# STM32_Board_with_IMU.net
KiCad netlist of a schematic drawn in Altium Designer
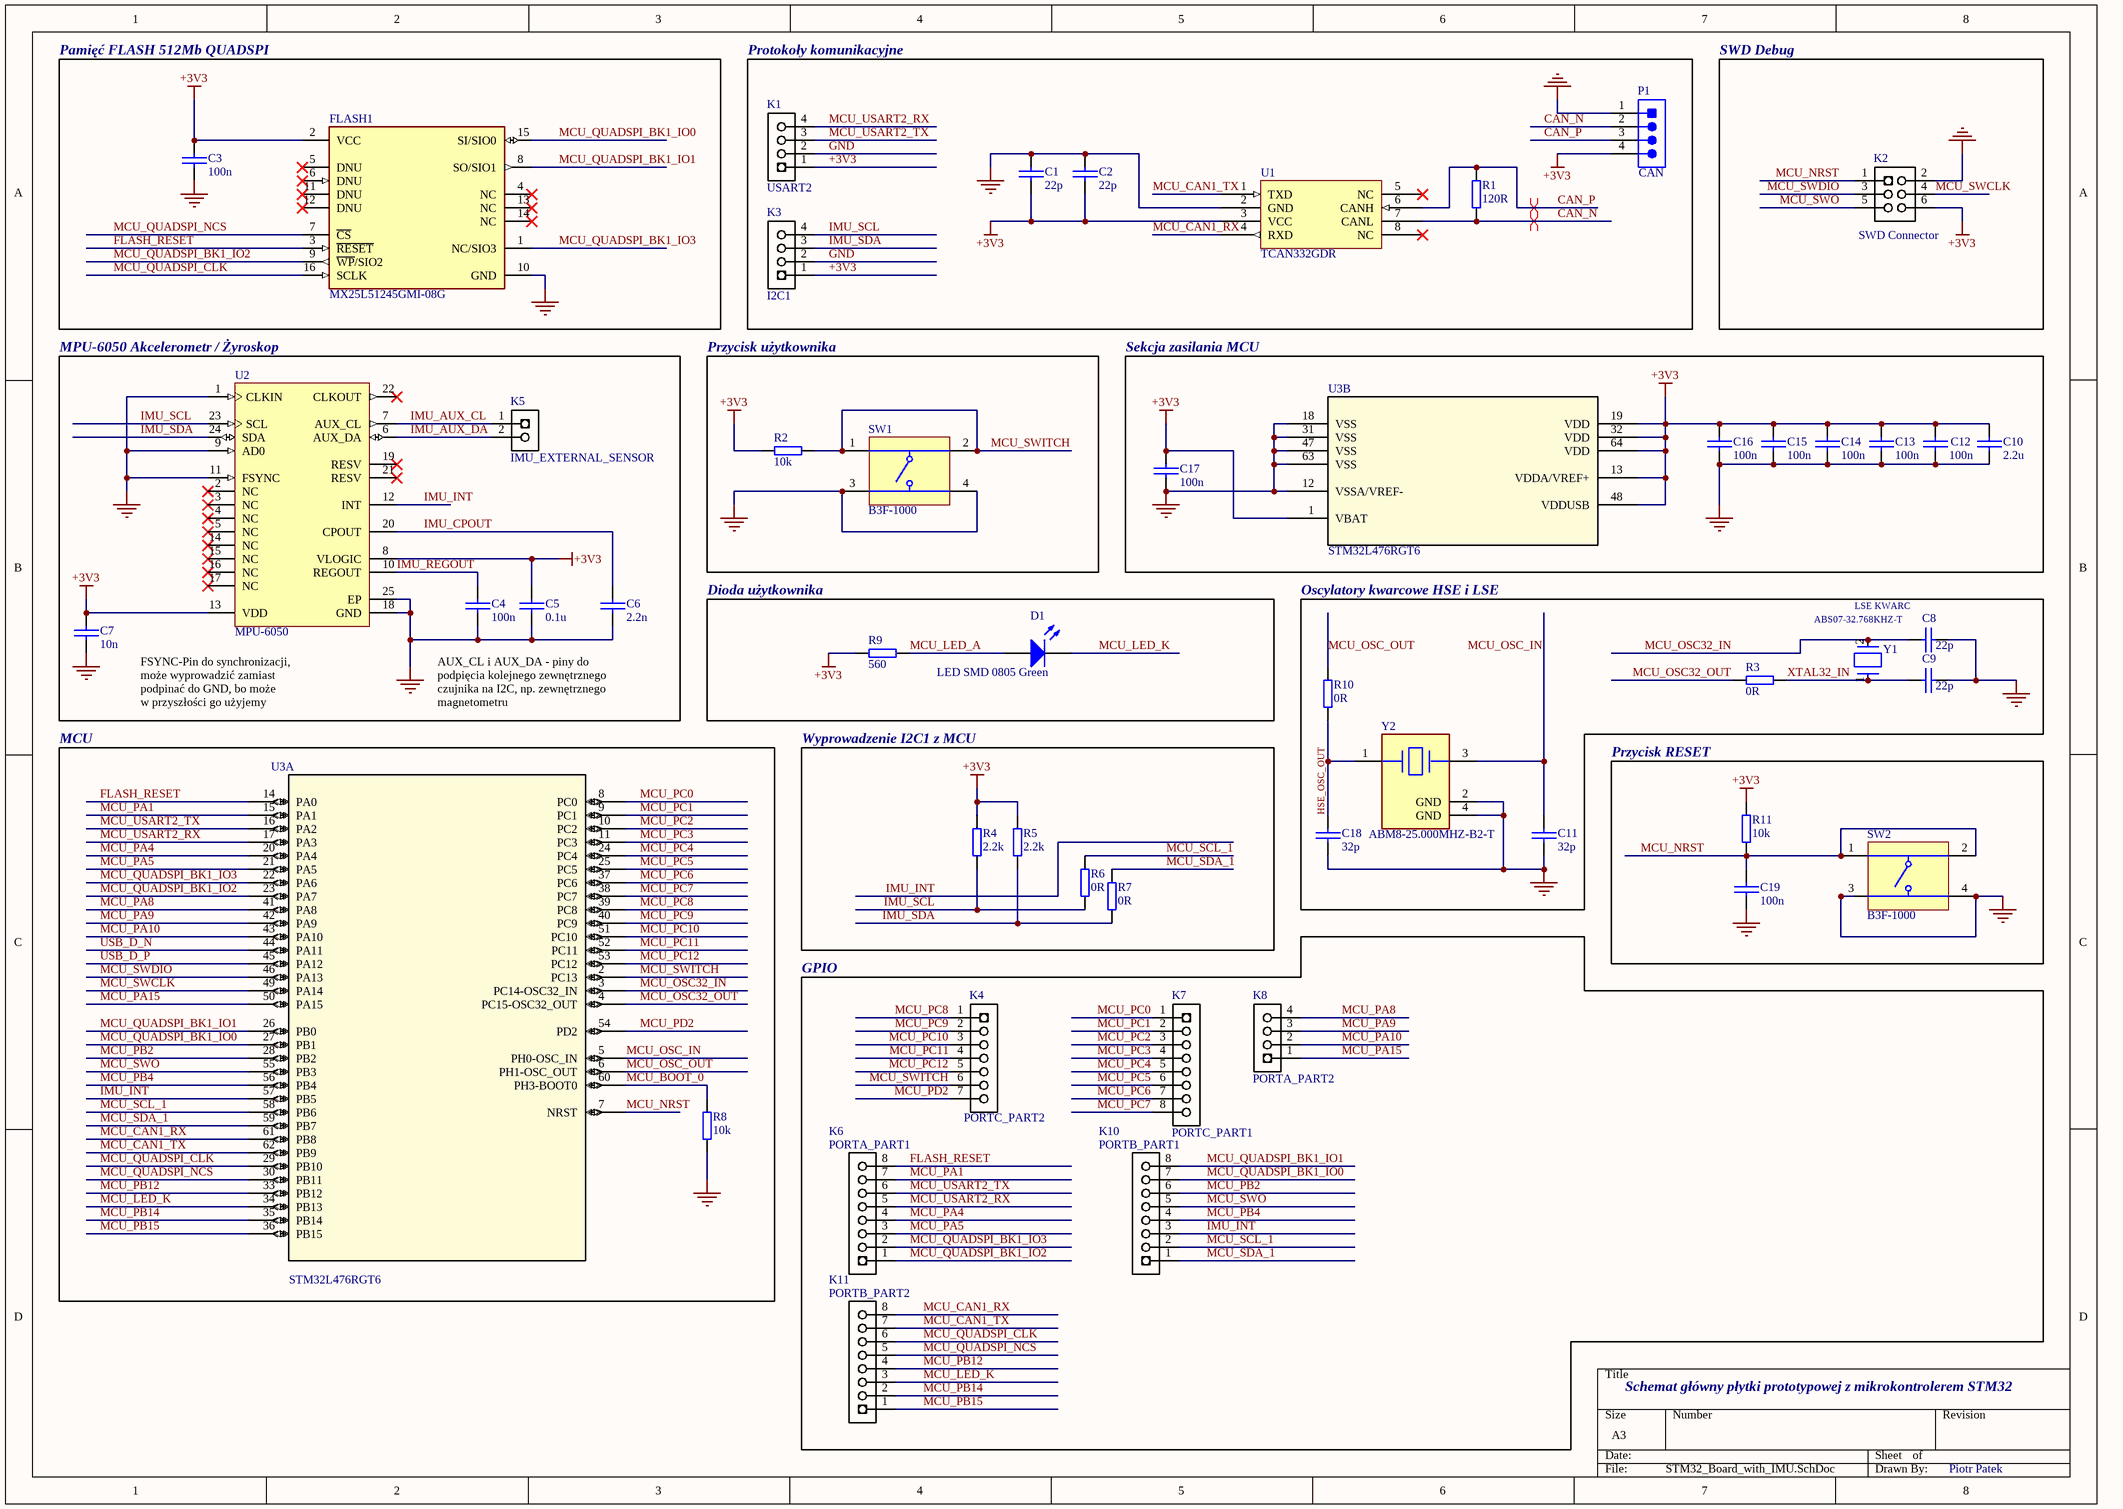
[diagram p0: STM32_Board_with_IMU.SchDoc]

(export (version "E")
  (design (tool "Eeschema 10.0.6"))
  (components
    (comp (ref "C1") (value "22p") (footprint "0805") (libsource (lib "Slawek_new") (part "Kondensator")))
    (comp (ref "C2") (value "22p") (footprint "0805") (libsource (lib "Slawek_new") (part "Kondensator")))
    (comp (ref "C3") (value "100n") (footprint "0805") (libsource (lib "Slawek_new") (part "Kondensator")))
    (comp (ref "C4") (value "100n") (footprint "0805") (libsource (lib "Slawek_new") (part "Kondensator")))
    (comp (ref "C5") (value "0.1u") (footprint "0805") (libsource (lib "Slawek_new") (part "Kondensator")))
    (comp (ref "C6") (value "2.2n") (footprint "0805") (libsource (lib "Slawek_new") (part "Kondensator")))
    (comp (ref "C7") (value "10n") (footprint "0805") (libsource (lib "Slawek_new") (part "Kondensator")))
    (comp (ref "C8") (value "22p") (footprint "0805") (libsource (lib "Slawek_new") (part "Kondensator")))
    (comp (ref "C9") (value "22p") (footprint "0805") (libsource (lib "Slawek_new") (part "Kondensator")))
    (comp (ref "C10") (value "2.2u") (footprint "0805") (libsource (lib "Slawek_new") (part "Kondensator")))
    (comp (ref "C11") (value "32p") (footprint "0805") (libsource (lib "Slawek_new") (part "Kondensator")))
    (comp (ref "C12") (value "100n") (footprint "0805") (libsource (lib "Slawek_new") (part "Kondensator")))
    (comp (ref "C13") (value "100n") (footprint "0805") (libsource (lib "Slawek_new") (part "Kondensator")))
    (comp (ref "C14") (value "100n") (footprint "0805") (libsource (lib "Slawek_new") (part "Kondensator")))
    (comp (ref "C15") (value "100n") (footprint "0805") (libsource (lib "Slawek_new") (part "Kondensator")))
    (comp (ref "C16") (value "100n") (footprint "0805") (libsource (lib "Slawek_new") (part "Kondensator")))
    (comp (ref "C17") (value "100n") (footprint "0805") (libsource (lib "Slawek_new") (part "Kondensator")))
    (comp (ref "C18") (value "32p") (footprint "0805") (libsource (lib "Slawek_new") (part "Kondensator")))
    (comp (ref "C19") (value "100n") (footprint "0805") (libsource (lib "Slawek_new") (part "Kondensator")))
    (comp (ref "D1")
      (value "LED SMD 0805 Green")
      (footprint "0805_PAD")
      (description "WURTH ELEKTRONIK - 150080GS75000 - LED, Green, SMD, 0805, 30 mA, 3.2 V, 520 nm")
      (fields
        (field (name "MANUFACTURER") "Wurth Electronics")
        (field (name "MANUFACTURER PART NUMBER") "150080GS75000")
      )
      (libsource (lib "BibliotekaPiotrek") (part "LED SMD 0805 Green"))
    )
    (comp (ref "FLASH1")
      (value "MX25L51245GMI-08G")
      (footprint "FP-MX25L51245GMI-08G-IPC_C")
      (description "IC FLASH 512MBIT SPI/QUAD 16SOP")
      (libsource (lib "Altium Content Vault") (part "66e4bce8553d63856ccc32a245ce7da"))
    )
    (comp (ref "K1")
      (value "USART2")
      (footprint "HEADER-1X4")
      (libsource (lib "vh_altium_library") (part "HEADER-1X4"))
    )
    (comp (ref "K2")
      (value "SWD Connector")
      (footprint "HEADER-2X3")
      (libsource (lib "vh_altium_library") (part "HEADER-2X3"))
    )
    (comp (ref "K3")
      (value "I2C1")
      (footprint "HEADER-1X4")
      (libsource (lib "vh_altium_library") (part "HEADER-1X4"))
    )
    (comp (ref "K4")
      (value "PORTC_PART2")
      (footprint "HEADER-1X7")
      (libsource (lib "vh_altium_library") (part "HEADER-1X7"))
    )
    (comp (ref "K5")
      (value "IMU_EXTERNAL_SENSOR")
      (footprint "HEADER-1X2")
      (libsource (lib "vh_altium_library") (part "HEADER-1X2"))
    )
    (comp (ref "K6")
      (value "PORTA_PART1")
      (footprint "HEADER-1X8")
      (libsource (lib "vh_altium_library") (part "HEADER-1X8"))
    )
    (comp (ref "K7")
      (value "PORTC_PART1")
      (footprint "HEADER-1X8")
      (libsource (lib "vh_altium_library") (part "HEADER-1X8"))
    )
    (comp (ref "K8")
      (value "PORTA_PART2")
      (footprint "HEADER-1X4")
      (libsource (lib "vh_altium_library") (part "HEADER-1X4"))
    )
    (comp (ref "K10")
      (value "PORTB_PART1")
      (footprint "HEADER-1X8")
      (libsource (lib "vh_altium_library") (part "HEADER-1X8"))
    )
    (comp (ref "K11")
      (value "PORTB_PART2")
      (footprint "HEADER-1X8")
      (libsource (lib "vh_altium_library") (part "HEADER-1X8"))
    )
    (comp (ref "P1")
      (value "CAN")
      (footprint "TECO-640456-4")
      (description "Male Header, Pitch 2.54 mm, 1 x 4 Position, Height 10.03 mm, Tail Length 3.56 mm, RoHS, Bulk")
      (fields (field (name "MANUFACTURER") "TE Connectivity"))
      (libsource (lib "Altium Content Vault") (part "CN-1P-M-R4"))
    )
    (comp (ref "R1") (value "120R") (footprint "0805") (libsource (lib "Slawek_new") (part "Rezystor")))
    (comp (ref "R2") (value "10k") (footprint "0805") (libsource (lib "Slawek_new") (part "Rezystor")))
    (comp (ref "R3") (value "0R") (footprint "0805") (libsource (lib "Slawek_new") (part "Rezystor")))
    (comp (ref "R4") (value "2.2k") (footprint "0805") (libsource (lib "Slawek_new") (part "Rezystor")))
    (comp (ref "R5") (value "2.2k") (footprint "0805") (libsource (lib "Slawek_new") (part "Rezystor")))
    (comp (ref "R6") (value "0R") (footprint "0805") (libsource (lib "Slawek_new") (part "Rezystor")))
    (comp (ref "R7") (value "0R") (footprint "0805") (libsource (lib "Slawek_new") (part "Rezystor")))
    (comp (ref "R8") (value "10k") (footprint "0805") (libsource (lib "Slawek_new") (part "Rezystor")))
    (comp (ref "R9") (value "560") (footprint "0805") (libsource (lib "Slawek_new") (part "Rezystor")))
    (comp (ref "R10") (value "0R") (footprint "0805") (libsource (lib "Slawek_new") (part "Rezystor")))
    (comp (ref "R11") (value "10k") (footprint "0805") (libsource (lib "Slawek_new") (part "Rezystor")))
    (comp (ref "SW1")
      (value "B3F-1000")
      (footprint "OMRON-B3F-1000-4_V")
      (description "Tactile Switch, SPST-NO, 0.05 A, 5 to 24 V, -25 to 70 degC, 4-Pin THD, RoHS, Bulk")
      (libsource (lib "Altium Content Vault") (part "SW-SPST-4_A"))
    )
    (comp (ref "SW2")
      (value "B3F-1000")
      (footprint "OMRON-B3F-1000-4_V")
      (description "Tactile Switch, SPST-NO, 0.05 A, 5 to 24 V, -25 to 70 degC, 4-Pin THD, RoHS, Bulk")
      (libsource (lib "Altium Content Vault") (part "SW-SPST-4_A"))
    )
    (comp (ref "U1")
      (value "TCAN332GDR")
      (footprint "SOIC-8_x1")
      (description "Can Transceiver")
      (libsource (lib "BibliotekaPiotrek") (part "TCAN332GDR"))
    )
    (comp (ref "U2")
      (value "MPU-6050")
      (footprint "IS-QFN-24_V")
      (fields (field (name "MANUFACTURER") "InvenSense"))
      (libsource (lib "Altium Content Vault") (part "IS-MPU-6050-QFN-24"))
    )
    (comp (ref "U3")
      (value "STM32L476RGT6")
      (footprint "LQFP64-10x10mm_STM")
      (description "No Description Available")
      (libsource (lib "STM32L476RGT6") (part "STM32L476RGT6"))
    )
    (comp (ref "Y1")
      (value "ABS07-32.768KHZ-T")
      (footprint "FP-ABS07-MFG")
      (description "Crystal 32.768kHz ±20ppm (Tol) 12.5pF FUND 70kΩ 2-Pin CSMD T/R")
      (fields (field (name "TOLERANCE") "20ppm"))
      (libsource (lib "Altium Content Vault") (part "c23a69dc6c9e2f18f2079038eb95dd1"))
    )
    (comp (ref "Y2")
      (value "ABM8-25.000MHZ-B2-T")
      (footprint "FP-ABM8-MFG")
      (description "Crystal 25MHz ±20ppm 18pF SMD-4 3.2mm x 2.5mm")
      (fields (field (name "TOLERANCE") "20ppm"))
      (libsource (lib "Altium Content Vault") (part "dfdb7f9a12507849fb681da9a70121c"))
    )
  )
  (nets
    (net (code "1") (name "+3V3") (class "Default")
      (node (ref "C1") (pin "2") (pinfunction "2_2") (pintype "passive"))
      (node (ref "C10") (pin "2") (pinfunction "2_2") (pintype "passive"))
      (node (ref "C12") (pin "2") (pinfunction "2_2") (pintype "passive"))
      (node (ref "C13") (pin "2") (pinfunction "2_2") (pintype "passive"))
      (node (ref "C14") (pin "2") (pinfunction "2_2") (pintype "passive"))
      (node (ref "C15") (pin "2") (pinfunction "2_2") (pintype "passive"))
      (node (ref "C16") (pin "2") (pinfunction "2_2") (pintype "passive"))
      (node (ref "C17") (pin "1") (pinfunction "1_1") (pintype "passive"))
      (node (ref "C2") (pin "2") (pinfunction "2_2") (pintype "passive"))
      (node (ref "C3") (pin "1") (pinfunction "1_1") (pintype "passive"))
      (node (ref "C5") (pin "1") (pinfunction "1_1") (pintype "passive"))
      (node (ref "C7") (pin "1") (pinfunction "1_1") (pintype "passive"))
      (node (ref "FLASH1") (pin "2") (pinfunction "VCC_2") (pintype "power_in"))
      (node (ref "K1") (pin "1") (pintype "passive"))
      (node (ref "K2") (pin "6") (pintype "passive"))
      (node (ref "K3") (pin "1") (pintype "passive"))
      (node (ref "P1") (pin "4") (pinfunction "4_4") (pintype "passive"))
      (node (ref "R11") (pin "1") (pintype "passive"))
      (node (ref "R2") (pin "1") (pintype "passive"))
      (node (ref "R4") (pin "2") (pintype "passive"))
      (node (ref "R5") (pin "2") (pintype "passive"))
      (node (ref "R9") (pin "1") (pintype "passive"))
      (node (ref "U1") (pin "3") (pinfunction "VCC_3") (pintype "passive"))
      (node (ref "U2") (pin "13") (pinfunction "VDD_13") (pintype "power_in"))
      (node (ref "U2") (pin "8") (pinfunction "VLOGIC_8") (pintype "power_in"))
      (node (ref "U3") (pin "1") (pinfunction "VBAT_1") (pintype "power_in"))
      (node (ref "U3") (pin "13") (pinfunction "VDDA/VREF+_13") (pintype "power_in"))
      (node (ref "U3") (pin "19") (pinfunction "VDD_19") (pintype "power_in"))
      (node (ref "U3") (pin "32") (pinfunction "VDD_32") (pintype "power_in"))
      (node (ref "U3") (pin "48") (pinfunction "VDDUSB_48") (pintype "power_in"))
      (node (ref "U3") (pin "64") (pinfunction "VDD_64") (pintype "power_in"))
    )
    (net (code "2") (name "/CAN_N") (class "Default")
      (node (ref "P1") (pin "2") (pinfunction "2_2") (pintype "passive"))
      (node (ref "R1") (pin "1") (pintype "passive"))
      (node (ref "U1") (pin "7") (pinfunction "CANL_7") (pintype "passive"))
    )
    (net (code "3") (name "/CAN_P") (class "Default")
      (node (ref "P1") (pin "3") (pinfunction "3_3") (pintype "passive"))
      (node (ref "R1") (pin "2") (pintype "passive"))
      (node (ref "U1") (pin "6") (pinfunction "CANH_6") (pintype "input"))
    )
    (net (code "4") (name "/FLASH_RESET") (class "Default")
      (node (ref "FLASH1") (pin "3") (pinfunction "~{RESET}_3") (pintype "input"))
      (node (ref "K6") (pin "8") (pintype "passive"))
      (node (ref "U3") (pin "14") (pinfunction "PA0_14") (pintype "bidirectional"))
    )
    (net (code "5") (name "/HSE_OSC_OUT") (class "Default")
      (node (ref "C18") (pin "1") (pinfunction "1_1") (pintype "passive"))
      (node (ref "R10") (pin "1") (pintype "passive"))
      (node (ref "Y2") (pin "1") (pinfunction "1_1") (pintype "passive"))
    )
    (net (code "6") (name "/IMU_AUX_CL") (class "Default")
      (node (ref "K5") (pin "1") (pintype "passive"))
      (node (ref "U2") (pin "7") (pinfunction "AUX_CL_7") (pintype "output"))
    )
    (net (code "7") (name "/IMU_AUX_DA") (class "Default")
      (node (ref "K5") (pin "2") (pintype "passive"))
      (node (ref "U2") (pin "6") (pinfunction "AUX_DA_6") (pintype "bidirectional"))
    )
    (net (code "8") (name "/IMU_CPOUT") (class "Default")
      (node (ref "C6") (pin "1") (pinfunction "1_1") (pintype "passive"))
      (node (ref "U2") (pin "20") (pinfunction "CPOUT_20") (pintype "passive"))
    )
    (net (code "9") (name "/IMU_INT") (class "Default")
      (node (ref "K10") (pin "3") (pintype "passive"))
      (node (ref "U2") (pin "12") (pinfunction "INT_12") (pintype "open_collector"))
      (node (ref "U3") (pin "57") (pinfunction "PB5_57") (pintype "bidirectional"))
    )
    (net (code "10") (name "/IMU_REGOUT") (class "Default")
      (node (ref "C4") (pin "1") (pinfunction "1_1") (pintype "passive"))
      (node (ref "U2") (pin "10") (pinfunction "REGOUT_10") (pintype "passive"))
    )
    (net (code "11") (name "/IMU_SCL") (class "Default")
      (node (ref "K3") (pin "4") (pintype "passive"))
      (node (ref "R4") (pin "1") (pintype "passive"))
      (node (ref "R6") (pin "1") (pintype "passive"))
      (node (ref "U2") (pin "23") (pinfunction "SCL_23") (pintype "input"))
    )
    (net (code "12") (name "/IMU_SDA") (class "Default")
      (node (ref "K3") (pin "3") (pintype "passive"))
      (node (ref "R5") (pin "1") (pintype "passive"))
      (node (ref "R7") (pin "1") (pintype "passive"))
      (node (ref "U2") (pin "24") (pinfunction "SDA_24") (pintype "bidirectional"))
    )
    (net (code "13") (name "/MCU_BOOT_0") (class "Default")
      (node (ref "R8") (pin "1") (pintype "passive"))
      (node (ref "U3") (pin "60") (pinfunction "PH3-BOOT0_60") (pintype "bidirectional"))
    )
    (net (code "14") (name "/MCU_CAN1_RX") (class "Default")
      (node (ref "K11") (pin "8") (pintype "passive"))
      (node (ref "U1") (pin "4") (pinfunction "RXD_4") (pintype "output"))
      (node (ref "U3") (pin "61") (pinfunction "PB8_61") (pintype "bidirectional"))
    )
    (net (code "15") (name "/MCU_CAN1_TX") (class "Default")
      (node (ref "K11") (pin "7") (pintype "passive"))
      (node (ref "U1") (pin "1") (pinfunction "TXD_1") (pintype "input"))
      (node (ref "U3") (pin "62") (pinfunction "PB9_62") (pintype "bidirectional"))
    )
    (net (code "16") (name "/MCU_LED_A") (class "Default")
      (node (ref "D1") (pin "2") (pinfunction "A_2") (pintype "passive"))
      (node (ref "R9") (pin "2") (pintype "passive"))
    )
    (net (code "17") (name "/MCU_LED_K") (class "Default")
      (node (ref "D1") (pin "1") (pinfunction "K_1") (pintype "passive"))
      (node (ref "K11") (pin "3") (pintype "passive"))
      (node (ref "U3") (pin "34") (pinfunction "PB13_34") (pintype "bidirectional"))
    )
    (net (code "18") (name "/MCU_NRST") (class "Default")
      (node (ref "C19") (pin "2") (pinfunction "2_2") (pintype "passive"))
      (node (ref "K2") (pin "1") (pintype "passive"))
      (node (ref "R11") (pin "2") (pintype "passive"))
      (node (ref "SW2") (pin "1") (pinfunction "1_1") (pintype "passive"))
      (node (ref "SW2") (pin "2") (pinfunction "2_2") (pintype "passive"))
      (node (ref "U3") (pin "7") (pinfunction "NRST_7") (pintype "bidirectional"))
    )
    (net (code "19") (name "/MCU_OSC32_IN") (class "Default")
      (node (ref "C8") (pin "2") (pinfunction "2_2") (pintype "passive"))
      (node (ref "U3") (pin "3") (pinfunction "PC14-OSC32_IN_3") (pintype "bidirectional"))
      (node (ref "Y1") (pin "2") (pinfunction "2_2") (pintype "passive"))
    )
    (net (code "20") (name "/MCU_OSC32_OUT") (class "Default")
      (node (ref "R3") (pin "1") (pintype "passive"))
      (node (ref "U3") (pin "4") (pinfunction "PC15-OSC32_OUT_4") (pintype "bidirectional"))
    )
    (net (code "21") (name "/MCU_OSC_IN") (class "Default")
      (node (ref "C11") (pin "2") (pinfunction "2_2") (pintype "passive"))
      (node (ref "U3") (pin "5") (pinfunction "PH0-OSC_IN_5") (pintype "bidirectional"))
      (node (ref "Y2") (pin "3") (pinfunction "3_3") (pintype "passive"))
    )
    (net (code "22") (name "/MCU_OSC_OUT") (class "Default")
      (node (ref "R10") (pin "2") (pintype "passive"))
      (node (ref "U3") (pin "6") (pinfunction "PH1-OSC_OUT_6") (pintype "bidirectional"))
    )
    (net (code "23") (name "/MCU_PA1") (class "Default")
      (node (ref "K6") (pin "7") (pintype "passive"))
      (node (ref "U3") (pin "15") (pinfunction "PA1_15") (pintype "bidirectional"))
    )
    (net (code "24") (name "/MCU_PA4") (class "Default")
      (node (ref "K6") (pin "4") (pintype "passive"))
      (node (ref "U3") (pin "20") (pinfunction "PA4_20") (pintype "bidirectional"))
    )
    (net (code "25") (name "/MCU_PA5") (class "Default")
      (node (ref "K6") (pin "3") (pintype "passive"))
      (node (ref "U3") (pin "21") (pinfunction "PA5_21") (pintype "bidirectional"))
    )
    (net (code "26") (name "/MCU_PA8") (class "Default")
      (node (ref "K8") (pin "4") (pintype "passive"))
      (node (ref "U3") (pin "41") (pinfunction "PA8_41") (pintype "bidirectional"))
    )
    (net (code "27") (name "/MCU_PA9") (class "Default")
      (node (ref "K8") (pin "3") (pintype "passive"))
      (node (ref "U3") (pin "42") (pinfunction "PA9_42") (pintype "bidirectional"))
    )
    (net (code "28") (name "/MCU_PA10") (class "Default")
      (node (ref "K8") (pin "2") (pintype "passive"))
      (node (ref "U3") (pin "43") (pinfunction "PA10_43") (pintype "bidirectional"))
    )
    (net (code "29") (name "/MCU_PA15") (class "Default")
      (node (ref "K8") (pin "1") (pintype "passive"))
      (node (ref "U3") (pin "50") (pinfunction "PA15_50") (pintype "bidirectional"))
    )
    (net (code "30") (name "/MCU_PB2") (class "Default")
      (node (ref "K10") (pin "6") (pintype "passive"))
      (node (ref "U3") (pin "28") (pinfunction "PB2_28") (pintype "bidirectional"))
    )
    (net (code "31") (name "/MCU_PB4") (class "Default")
      (node (ref "K10") (pin "4") (pintype "passive"))
      (node (ref "U3") (pin "56") (pinfunction "PB4_56") (pintype "bidirectional"))
    )
    (net (code "32") (name "/MCU_PB12") (class "Default")
      (node (ref "K11") (pin "4") (pintype "passive"))
      (node (ref "U3") (pin "33") (pinfunction "PB12_33") (pintype "bidirectional"))
    )
    (net (code "33") (name "/MCU_PB14") (class "Default")
      (node (ref "K11") (pin "2") (pintype "passive"))
      (node (ref "U3") (pin "35") (pinfunction "PB14_35") (pintype "bidirectional"))
    )
    (net (code "34") (name "/MCU_PB15") (class "Default")
      (node (ref "K11") (pin "1") (pintype "passive"))
      (node (ref "U3") (pin "36") (pinfunction "PB15_36") (pintype "bidirectional"))
    )
    (net (code "35") (name "/MCU_PC0") (class "Default")
      (node (ref "K7") (pin "1") (pintype "passive"))
      (node (ref "U3") (pin "8") (pinfunction "PC0_8") (pintype "bidirectional"))
    )
    (net (code "36") (name "/MCU_PC1") (class "Default")
      (node (ref "K7") (pin "2") (pintype "passive"))
      (node (ref "U3") (pin "9") (pinfunction "PC1_9") (pintype "bidirectional"))
    )
    (net (code "37") (name "/MCU_PC2") (class "Default")
      (node (ref "K7") (pin "3") (pintype "passive"))
      (node (ref "U3") (pin "10") (pinfunction "PC2_10") (pintype "bidirectional"))
    )
    (net (code "38") (name "/MCU_PC3") (class "Default")
      (node (ref "K7") (pin "4") (pintype "passive"))
      (node (ref "U3") (pin "11") (pinfunction "PC3_11") (pintype "bidirectional"))
    )
    (net (code "39") (name "/MCU_PC4") (class "Default")
      (node (ref "K7") (pin "5") (pintype "passive"))
      (node (ref "U3") (pin "24") (pinfunction "PC4_24") (pintype "bidirectional"))
    )
    (net (code "40") (name "/MCU_PC5") (class "Default")
      (node (ref "K7") (pin "6") (pintype "passive"))
      (node (ref "U3") (pin "25") (pinfunction "PC5_25") (pintype "bidirectional"))
    )
    (net (code "41") (name "/MCU_PC6") (class "Default")
      (node (ref "K7") (pin "7") (pintype "passive"))
      (node (ref "U3") (pin "37") (pinfunction "PC6_37") (pintype "bidirectional"))
    )
    (net (code "42") (name "/MCU_PC7") (class "Default")
      (node (ref "K7") (pin "8") (pintype "passive"))
      (node (ref "U3") (pin "38") (pinfunction "PC7_38") (pintype "bidirectional"))
    )
    (net (code "43") (name "/MCU_PC8") (class "Default")
      (node (ref "K4") (pin "1") (pintype "passive"))
      (node (ref "U3") (pin "39") (pinfunction "PC8_39") (pintype "bidirectional"))
    )
    (net (code "44") (name "/MCU_PC9") (class "Default")
      (node (ref "K4") (pin "2") (pintype "passive"))
      (node (ref "U3") (pin "40") (pinfunction "PC9_40") (pintype "bidirectional"))
    )
    (net (code "45") (name "/MCU_PC10") (class "Default")
      (node (ref "K4") (pin "3") (pintype "passive"))
      (node (ref "U3") (pin "51") (pinfunction "PC10_51") (pintype "bidirectional"))
    )
    (net (code "46") (name "/MCU_PC11") (class "Default")
      (node (ref "K4") (pin "4") (pintype "passive"))
      (node (ref "U3") (pin "52") (pinfunction "PC11_52") (pintype "bidirectional"))
    )
    (net (code "47") (name "/MCU_PC12") (class "Default")
      (node (ref "K4") (pin "5") (pintype "passive"))
      (node (ref "U3") (pin "53") (pinfunction "PC12_53") (pintype "bidirectional"))
    )
    (net (code "48") (name "/MCU_PD2") (class "Default")
      (node (ref "K4") (pin "7") (pintype "passive"))
      (node (ref "U3") (pin "54") (pinfunction "PD2_54") (pintype "bidirectional"))
    )
    (net (code "49") (name "/MCU_QUADSPI_BK1_IO0") (class "Default")
      (node (ref "FLASH1") (pin "15") (pinfunction "SI/SIO0_15") (pintype "bidirectional"))
      (node (ref "K10") (pin "7") (pintype "passive"))
      (node (ref "U3") (pin "27") (pinfunction "PB1_27") (pintype "bidirectional"))
    )
    (net (code "50") (name "/MCU_QUADSPI_BK1_IO1") (class "Default")
      (node (ref "FLASH1") (pin "8") (pinfunction "SO/SIO1_8") (pintype "output"))
      (node (ref "K10") (pin "8") (pintype "passive"))
      (node (ref "U3") (pin "26") (pinfunction "PB0_26") (pintype "bidirectional"))
    )
    (net (code "51") (name "/MCU_QUADSPI_BK1_IO2") (class "Default")
      (node (ref "FLASH1") (pin "9") (pinfunction "~{WP}/SIO2_9") (pintype "output"))
      (node (ref "K6") (pin "1") (pintype "passive"))
      (node (ref "U3") (pin "23") (pinfunction "PA7_23") (pintype "bidirectional"))
    )
    (net (code "52") (name "/MCU_QUADSPI_BK1_IO3") (class "Default")
      (node (ref "FLASH1") (pin "1") (pinfunction "NC/SIO3_1") (pintype "passive"))
      (node (ref "K6") (pin "2") (pintype "passive"))
      (node (ref "U3") (pin "22") (pinfunction "PA6_22") (pintype "bidirectional"))
    )
    (net (code "53") (name "/MCU_QUADSPI_CLK") (class "Default")
      (node (ref "FLASH1") (pin "16") (pinfunction "SCLK_16") (pintype "input"))
      (node (ref "K11") (pin "6") (pintype "passive"))
      (node (ref "U3") (pin "29") (pinfunction "PB10_29") (pintype "bidirectional"))
    )
    (net (code "54") (name "/MCU_QUADSPI_NCS") (class "Default")
      (node (ref "FLASH1") (pin "7") (pinfunction "~{CS}_7") (pintype "passive"))
      (node (ref "K11") (pin "5") (pintype "passive"))
      (node (ref "U3") (pin "30") (pinfunction "PB11_30") (pintype "bidirectional"))
    )
    (net (code "55") (name "/MCU_SCL_1") (class "Default")
      (node (ref "K10") (pin "2") (pintype "passive"))
      (node (ref "R6") (pin "2") (pintype "passive"))
      (node (ref "U3") (pin "58") (pinfunction "PB6_58") (pintype "bidirectional"))
    )
    (net (code "56") (name "/MCU_SDA_1") (class "Default")
      (node (ref "K10") (pin "1") (pintype "passive"))
      (node (ref "R7") (pin "2") (pintype "passive"))
      (node (ref "U3") (pin "59") (pinfunction "PB7_59") (pintype "bidirectional"))
    )
    (net (code "57") (name "/MCU_SWCLK") (class "Default")
      (node (ref "K2") (pin "4") (pintype "passive"))
      (node (ref "U3") (pin "49") (pinfunction "PA14_49") (pintype "bidirectional"))
    )
    (net (code "58") (name "/MCU_SWDIO") (class "Default")
      (node (ref "K2") (pin "3") (pintype "passive"))
      (node (ref "U3") (pin "46") (pinfunction "PA13_46") (pintype "bidirectional"))
    )
    (net (code "59") (name "/MCU_SWITCH") (class "Default")
      (node (ref "K4") (pin "6") (pintype "passive"))
      (node (ref "R2") (pin "2") (pintype "passive"))
      (node (ref "SW1") (pin "1") (pinfunction "1_1") (pintype "passive"))
      (node (ref "SW1") (pin "2") (pinfunction "2_2") (pintype "passive"))
      (node (ref "U3") (pin "2") (pinfunction "PC13_2") (pintype "bidirectional"))
    )
    (net (code "60") (name "/MCU_SWO") (class "Default")
      (node (ref "K10") (pin "5") (pintype "passive"))
      (node (ref "K2") (pin "5") (pintype "passive"))
      (node (ref "U3") (pin "55") (pinfunction "PB3_55") (pintype "bidirectional"))
    )
    (net (code "61") (name "/MCU_USART2_RX") (class "Default")
      (node (ref "K1") (pin "4") (pintype "passive"))
      (node (ref "K6") (pin "5") (pintype "passive"))
      (node (ref "U3") (pin "17") (pinfunction "PA3_17") (pintype "bidirectional"))
    )
    (net (code "62") (name "/MCU_USART2_TX") (class "Default")
      (node (ref "K1") (pin "3") (pintype "passive"))
      (node (ref "K6") (pin "6") (pintype "passive"))
      (node (ref "U3") (pin "16") (pinfunction "PA2_16") (pintype "bidirectional"))
    )
    (net (code "63") (name "/USB_D_N") (class "Default")
      (node (ref "U3") (pin "44") (pinfunction "PA11_44") (pintype "bidirectional"))
    )
    (net (code "64") (name "/USB_D_P") (class "Default")
      (node (ref "U3") (pin "45") (pinfunction "PA12_45") (pintype "bidirectional"))
    )
    (net (code "65") (name "/XTAL32_IN") (class "Default")
      (node (ref "C9") (pin "2") (pinfunction "2_2") (pintype "passive"))
      (node (ref "R3") (pin "2") (pintype "passive"))
      (node (ref "Y1") (pin "1") (pinfunction "1_1") (pintype "passive"))
    )
    (net (code "66") (name "GND") (class "Default")
      (node (ref "C1") (pin "1") (pinfunction "1_1") (pintype "passive"))
      (node (ref "C10") (pin "1") (pinfunction "1_1") (pintype "passive"))
      (node (ref "C11") (pin "1") (pinfunction "1_1") (pintype "passive"))
      (node (ref "C12") (pin "1") (pinfunction "1_1") (pintype "passive"))
      (node (ref "C13") (pin "1") (pinfunction "1_1") (pintype "passive"))
      (node (ref "C14") (pin "1") (pinfunction "1_1") (pintype "passive"))
      (node (ref "C15") (pin "1") (pinfunction "1_1") (pintype "passive"))
      (node (ref "C16") (pin "1") (pinfunction "1_1") (pintype "passive"))
      (node (ref "C17") (pin "2") (pinfunction "2_2") (pintype "passive"))
      (node (ref "C18") (pin "2") (pinfunction "2_2") (pintype "passive"))
      (node (ref "C19") (pin "1") (pinfunction "1_1") (pintype "passive"))
      (node (ref "C2") (pin "1") (pinfunction "1_1") (pintype "passive"))
      (node (ref "C3") (pin "2") (pinfunction "2_2") (pintype "passive"))
      (node (ref "C4") (pin "2") (pinfunction "2_2") (pintype "passive"))
      (node (ref "C5") (pin "2") (pinfunction "2_2") (pintype "passive"))
      (node (ref "C6") (pin "2") (pinfunction "2_2") (pintype "passive"))
      (node (ref "C7") (pin "2") (pinfunction "2_2") (pintype "passive"))
      (node (ref "C8") (pin "1") (pinfunction "1_1") (pintype "passive"))
      (node (ref "C9") (pin "1") (pinfunction "1_1") (pintype "passive"))
      (node (ref "FLASH1") (pin "10") (pinfunction "GND_10") (pintype "power_in"))
      (node (ref "K1") (pin "2") (pintype "passive"))
      (node (ref "K2") (pin "2") (pintype "passive"))
      (node (ref "K3") (pin "2") (pintype "passive"))
      (node (ref "P1") (pin "1") (pinfunction "1_1") (pintype "passive"))
      (node (ref "R8") (pin "2") (pintype "passive"))
      (node (ref "SW1") (pin "3") (pinfunction "3_3") (pintype "passive"))
      (node (ref "SW1") (pin "4") (pinfunction "4_4") (pintype "passive"))
      (node (ref "SW2") (pin "3") (pinfunction "3_3") (pintype "passive"))
      (node (ref "SW2") (pin "4") (pinfunction "4_4") (pintype "passive"))
      (node (ref "U1") (pin "2") (pinfunction "GND_2") (pintype "passive"))
      (node (ref "U2") (pin "1") (pinfunction "CLKIN_1") (pintype "input"))
      (node (ref "U2") (pin "11") (pinfunction "FSYNC_11") (pintype "input"))
      (node (ref "U2") (pin "18") (pinfunction "GND_18") (pintype "power_in"))
      (node (ref "U2") (pin "25") (pinfunction "EP_25") (pintype "power_in"))
      (node (ref "U2") (pin "9") (pinfunction "AD0_9") (pintype "input"))
      (node (ref "U3") (pin "12") (pinfunction "VSSA/VREF-_12") (pintype "power_in"))
      (node (ref "U3") (pin "18") (pinfunction "VSS_18") (pintype "power_in"))
      (node (ref "U3") (pin "31") (pinfunction "VSS_31") (pintype "power_in"))
      (node (ref "U3") (pin "47") (pinfunction "VSS_47") (pintype "power_in"))
      (node (ref "U3") (pin "63") (pinfunction "VSS_63") (pintype "power_in"))
      (node (ref "Y2") (pin "2") (pinfunction "GND_2") (pintype "power_in"))
      (node (ref "Y2") (pin "4") (pinfunction "GND_4") (pintype "power_in"))
    )
    (net (code "67") (name "unconnected-(FLASH1-DNU-Pad5)") (class "Default")
      (node (ref "FLASH1") (pin "5") (pinfunction "DNU_5") (pintype "passive+no_connect"))
    )
    (net (code "68") (name "unconnected-(FLASH1-DNU-Pad6)") (class "Default")
      (node (ref "FLASH1") (pin "6") (pinfunction "DNU_6") (pintype "input+no_connect"))
    )
    (net (code "69") (name "unconnected-(FLASH1-DNU-Pad11)") (class "Default")
      (node (ref "FLASH1") (pin "11") (pinfunction "DNU_11") (pintype "passive+no_connect"))
    )
    (net (code "70") (name "unconnected-(FLASH1-DNU-Pad12)") (class "Default")
      (node (ref "FLASH1") (pin "12") (pinfunction "DNU_12") (pintype "passive+no_connect"))
    )
    (net (code "71") (name "unconnected-(FLASH1-NC-Pad4)") (class "Default")
      (node (ref "FLASH1") (pin "4") (pinfunction "NC_4") (pintype "passive+no_connect"))
    )
    (net (code "72") (name "unconnected-(FLASH1-NC-Pad13)") (class "Default")
      (node (ref "FLASH1") (pin "13") (pinfunction "NC_13") (pintype "passive+no_connect"))
    )
    (net (code "73") (name "unconnected-(FLASH1-NC-Pad14)") (class "Default")
      (node (ref "FLASH1") (pin "14") (pinfunction "NC_14") (pintype "passive+no_connect"))
    )
    (net (code "74") (name "unconnected-(U1-NC-Pad5)") (class "Default")
      (node (ref "U1") (pin "5") (pinfunction "NC_5") (pintype "passive+no_connect"))
    )
    (net (code "75") (name "unconnected-(U1-NC-Pad8)") (class "Default")
      (node (ref "U1") (pin "8") (pinfunction "NC_8") (pintype "passive+no_connect"))
    )
    (net (code "76") (name "unconnected-(U2-CLKOUT-Pad22)") (class "Default")
      (node (ref "U2") (pin "22") (pinfunction "CLKOUT_22") (pintype "output+no_connect"))
    )
    (net (code "77") (name "unconnected-(U2-NC-Pad2)") (class "Default")
      (node (ref "U2") (pin "2") (pinfunction "NC_2") (pintype "passive+no_connect"))
    )
    (net (code "78") (name "unconnected-(U2-NC-Pad3)") (class "Default")
      (node (ref "U2") (pin "3") (pinfunction "NC_3") (pintype "passive+no_connect"))
    )
    (net (code "79") (name "unconnected-(U2-NC-Pad4)") (class "Default")
      (node (ref "U2") (pin "4") (pinfunction "NC_4") (pintype "passive+no_connect"))
    )
    (net (code "80") (name "unconnected-(U2-NC-Pad5)") (class "Default")
      (node (ref "U2") (pin "5") (pinfunction "NC_5") (pintype "passive+no_connect"))
    )
    (net (code "81") (name "unconnected-(U2-NC-Pad14)") (class "Default")
      (node (ref "U2") (pin "14") (pinfunction "NC_14") (pintype "passive+no_connect"))
    )
    (net (code "82") (name "unconnected-(U2-NC-Pad15)") (class "Default")
      (node (ref "U2") (pin "15") (pinfunction "NC_15") (pintype "passive+no_connect"))
    )
    (net (code "83") (name "unconnected-(U2-NC-Pad16)") (class "Default")
      (node (ref "U2") (pin "16") (pinfunction "NC_16") (pintype "passive+no_connect"))
    )
    (net (code "84") (name "unconnected-(U2-NC-Pad17)") (class "Default")
      (node (ref "U2") (pin "17") (pinfunction "NC_17") (pintype "passive+no_connect"))
    )
    (net (code "85") (name "unconnected-(U2-RESV-Pad19)") (class "Default")
      (node (ref "U2") (pin "19") (pinfunction "RESV_19") (pintype "passive+no_connect"))
    )
    (net (code "86") (name "unconnected-(U2-RESV-Pad21)") (class "Default")
      (node (ref "U2") (pin "21") (pinfunction "RESV_21") (pintype "passive+no_connect"))
    )
  )
)
